# h_sensor_safety.net
KiCad netlist of a schematic drawn in Altium Designer
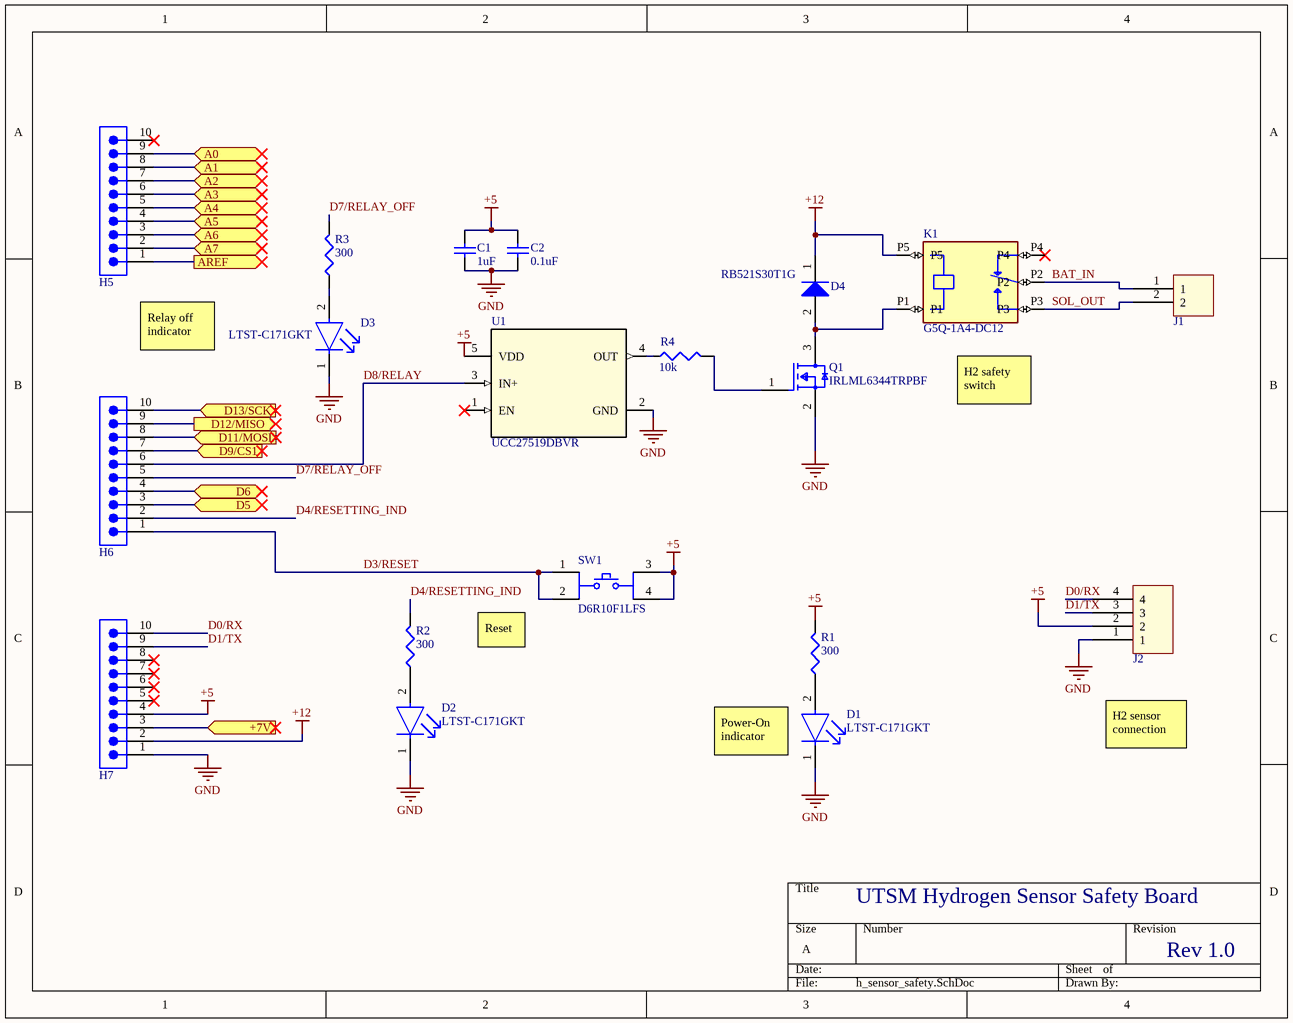
[diagram p0: h_sensor_safety.SchDoc]

(export (version "E")
  (design (tool "Eeschema 10.0.6"))
  (components
    (comp (ref "C1")
      (value "1uF")
      (footprint "0603c")
      (description "0603 Capacitor")
      (fields (field (name "PUBLISHER") "Altium Limited"))
      (libsource (lib "h_sensor_safety") (part "Cap"))
    )
    (comp (ref "C2")
      (value "0.1uF")
      (footprint "0603c")
      (description "0603 Capacitor")
      (fields (field (name "PUBLISHER") "Altium Limited"))
      (libsource (lib "h_sensor_safety") (part "Cap"))
    )
    (comp (ref "D1")
      (value "LTST-C171GKT")
      (footprint "FP-LTST-C171GKT-MFG")
      (description "LED GREEN CLEAR CHIP SMD")
      (libsource (lib "Altium Content Vault") (part "8706943c75ba83719d021d2fdc84c58"))
    )
    (comp (ref "D2")
      (value "LTST-C171GKT")
      (footprint "FP-LTST-C171GKT-MFG")
      (description "LED GREEN CLEAR CHIP SMD")
      (libsource (lib "Altium Content Vault") (part "8706943c75ba83719d021d2fdc84c58"))
    )
    (comp (ref "D3")
      (value "LTST-C171GKT")
      (footprint "FP-LTST-C171GKT-MFG")
      (description "LED GREEN CLEAR CHIP SMD")
      (libsource (lib "Altium Content Vault") (part "8706943c75ba83719d021d2fdc84c58"))
    )
    (comp (ref "D4")
      (value "RB521S30T1G")
      (footprint "ONSC-SOD-523-2-502-01_V")
      (description "Schottky Barrier Diode, 2-Pin SOD-523, Pb-Free, Tape and Reel")
      (fields (field (name "MANUFACTURER") "On Semiconductor"))
      (libsource (lib "Altium Content Vault") (part "ONSC-D-K1A2-2"))
    )
    (comp (ref "H5")
      (value "~")
      (footprint "61301011121")
      (description "WR-PHD Pin Header, THT, Vertical, pitch 2.54mm, 1 Row, 10P")
      (fields
        (field (name "MANUFACTURER PART NUMBER") "61301011121")
        (field (name "MANUFACTURER") "Wurth Elektronik")
      )
      (libsource (lib "h_sensor_safety") (part "61301011121"))
    )
    (comp (ref "H6")
      (value "~")
      (footprint "61301011121")
      (description "WR-PHD Pin Header, THT, Vertical, pitch 2.54mm, 1 Row, 10P")
      (fields
        (field (name "MANUFACTURER PART NUMBER") "61301011121")
        (field (name "MANUFACTURER") "Wurth Elektronik")
      )
      (libsource (lib "h_sensor_safety") (part "61301011121"))
    )
    (comp (ref "H7")
      (value "~")
      (footprint "61301011121")
      (description "WR-PHD Pin Header, THT, Vertical, pitch 2.54mm, 1 Row, 10P")
      (fields
        (field (name "MANUFACTURER PART NUMBER") "61301011121")
        (field (name "MANUFACTURER") "Wurth Elektronik")
      )
      (libsource (lib "h_sensor_safety") (part "61301011121"))
    )
    (comp (ref "J1")
      (value "header 2 pos minifit right angle")
      (footprint "h_sensor_safety:0039300020 minifit 2 pos")
      (libsource (lib "h_sensor_safety") (part "header 2 pos minifit right angle"))
    )
    (comp (ref "J2")
      (value "header 4 pos microfit right angle single row")
      (footprint "0436500401 MICROFIT 4 POS RIGHT ANGLE SINGLE ROW")
      (libsource (lib "h_sensor_safety") (part "header 4 pos microfit right angle single row"))
    )
    (comp (ref "K1")
      (value "G5Q-1A4-DC12")
      (footprint "G5Q-1A4-DC12")
      (fields (field (name "MF") "Omron Electronics"))
      (libsource (lib "h_sensor_safety") (part "G5Q-1A4-DC12"))
    )
    (comp (ref "Q1")
      (value "IRLML6344TRPBF")
      (footprint "FP-Micro3-MFG")
      (description "MOSFET N-CH 30V 2.7A SOT-23-3")
      (fields
        (field (name "MANUFACTURER PART NUMBER") "IRLML2030TRPBF")
        (field (name "OCTOPART") "https://octopart.com/irlml2030trpbf-infineon-65874966")
      )
      (libsource (lib "Altium Content Vault") (part "0a9ea7c96deaaede766a5b531c28de0"))
    )
    (comp (ref "R1")
      (value "300")
      (footprint "0603r")
      (description "SMD Resistor")
      (fields (field (name "Comment") "Res3") (field (name "PUBLISHER") "Altium Limited"))
      (libsource (lib "h_sensor_safety") (part "Res3"))
    )
    (comp (ref "R2")
      (value "300")
      (footprint "0603r")
      (description "SMD Resistor")
      (fields (field (name "Comment") "Res3") (field (name "PUBLISHER") "Altium Limited"))
      (libsource (lib "h_sensor_safety") (part "Res3"))
    )
    (comp (ref "R3")
      (value "300")
      (footprint "0603r")
      (description "SMD Resistor")
      (fields (field (name "Comment") "Res3") (field (name "PUBLISHER") "Altium Limited"))
      (libsource (lib "h_sensor_safety") (part "Res3"))
    )
    (comp (ref "R4")
      (value "10k")
      (footprint "0603r")
      (description "SMD Resistor")
      (fields (field (name "Comment") "Res3") (field (name "PUBLISHER") "Altium Limited"))
      (libsource (lib "h_sensor_safety") (part "Res3"))
    )
    (comp (ref "SW1")
      (value "D6R10F1LFS")
      (footprint "FP-D6R10F1LFS-MFG")
      (description "SWITCH PUSH SPST-NO 0.1A 32V")
      (libsource (lib "Altium Content Vault") (part "14b20f899b8ec0ab38832816b8a4cde"))
    )
    (comp (ref "U1")
      (value "UCC27519DBVR")
      (footprint "SOT95P280X145-5N")
      (description "Low side gate driver")
      (fields
        (field (name "ALTERNATE_PARTNUMBER") "UCC27519DBVT")
        (field (name "MANUFACTURER") "Texas Instruments")
        (field (name "COPYRIGHT") "Copyright (C) 2023 Ultra Librarian. All rights reserved.")
      )
      (libsource (lib "h_sensor_safety") (part "UCC27519DBVR"))
    )
  )
  (nets
    (net (code "1") (name "+5") (class "Default")
      (node (ref "C1") (pin "2") (pinfunction "2_2") (pintype "passive"))
      (node (ref "C2") (pin "2") (pinfunction "2_2") (pintype "passive"))
      (node (ref "H7") (pin "4") (pinfunction "4_4") (pintype "passive"))
      (node (ref "J2") (pin "2") (pinfunction "2_2") (pintype "passive"))
      (node (ref "R1") (pin "2") (pinfunction "2_2") (pintype "passive"))
      (node (ref "SW1") (pin "3") (pinfunction "3_3") (pintype "passive"))
      (node (ref "SW1") (pin "4") (pinfunction "4_4") (pintype "passive"))
      (node (ref "U1") (pin "5") (pinfunction "VDD_5") (pintype "power_in"))
    )
    (net (code "2") (name "+12") (class "Default")
      (node (ref "D4") (pin "1") (pinfunction "K_1") (pintype "passive"))
      (node (ref "H7") (pin "2") (pinfunction "2_2") (pintype "passive"))
      (node (ref "K1") (pin "P5") (pinfunction "P5_P5") (pintype "bidirectional"))
    )
    (net (code "3") (name "/+7V") (class "Default")
      (node (ref "H7") (pin "3") (pinfunction "3_3") (pintype "passive"))
    )
    (net (code "4") (name "/A0") (class "Default")
      (node (ref "H5") (pin "9") (pinfunction "9_9") (pintype "passive"))
    )
    (net (code "5") (name "/A1") (class "Default")
      (node (ref "H5") (pin "8") (pinfunction "8_8") (pintype "passive"))
    )
    (net (code "6") (name "/A2") (class "Default")
      (node (ref "H5") (pin "7") (pinfunction "7_7") (pintype "passive"))
    )
    (net (code "7") (name "/A3") (class "Default")
      (node (ref "H5") (pin "6") (pinfunction "6_6") (pintype "passive"))
    )
    (net (code "8") (name "/A4") (class "Default")
      (node (ref "H5") (pin "5") (pinfunction "5_5") (pintype "passive"))
    )
    (net (code "9") (name "/A5") (class "Default")
      (node (ref "H5") (pin "4") (pinfunction "4_4") (pintype "passive"))
    )
    (net (code "10") (name "/A6") (class "Default")
      (node (ref "H5") (pin "3") (pinfunction "3_3") (pintype "passive"))
    )
    (net (code "11") (name "/A7") (class "Default")
      (node (ref "H5") (pin "2") (pinfunction "2_2") (pintype "passive"))
    )
    (net (code "12") (name "/AREF") (class "Default")
      (node (ref "H5") (pin "1") (pinfunction "1_1") (pintype "passive"))
    )
    (net (code "13") (name "/BAT_IN") (class "Default")
      (node (ref "J1") (pin "1") (pinfunction "1_1") (pintype "passive"))
      (node (ref "K1") (pin "P2") (pinfunction "P2_P2") (pintype "bidirectional"))
    )
    (net (code "14") (name "/D0{slash}RX") (class "Default")
      (node (ref "H7") (pin "10") (pinfunction "10_10") (pintype "passive"))
      (node (ref "J2") (pin "4") (pinfunction "4_4") (pintype "passive"))
    )
    (net (code "15") (name "/D1{slash}TX") (class "Default")
      (node (ref "H7") (pin "9") (pinfunction "9_9") (pintype "passive"))
      (node (ref "J2") (pin "3") (pinfunction "3_3") (pintype "passive"))
    )
    (net (code "16") (name "/D3{slash}RESET") (class "Default")
      (node (ref "H6") (pin "1") (pinfunction "1_1") (pintype "passive"))
      (node (ref "SW1") (pin "1") (pinfunction "1_1") (pintype "passive"))
      (node (ref "SW1") (pin "2") (pinfunction "2_2") (pintype "passive"))
    )
    (net (code "17") (name "/D4{slash}RESETTING_IND") (class "Default")
      (node (ref "H6") (pin "2") (pinfunction "2_2") (pintype "passive"))
      (node (ref "R2") (pin "2") (pinfunction "2_2") (pintype "passive"))
    )
    (net (code "18") (name "/D5") (class "Default")
      (node (ref "H6") (pin "3") (pinfunction "3_3") (pintype "passive"))
    )
    (net (code "19") (name "/D6") (class "Default")
      (node (ref "H6") (pin "4") (pinfunction "4_4") (pintype "passive"))
    )
    (net (code "20") (name "/D7{slash}RELAY_OFF") (class "Default")
      (node (ref "H6") (pin "5") (pinfunction "5_5") (pintype "passive"))
      (node (ref "R3") (pin "2") (pinfunction "2_2") (pintype "passive"))
    )
    (net (code "21") (name "/D8{slash}RELAY") (class "Default")
      (node (ref "H6") (pin "6") (pinfunction "6_6") (pintype "passive"))
      (node (ref "U1") (pin "3") (pinfunction "IN+_3") (pintype "input"))
    )
    (net (code "22") (name "/D9{slash}CS1") (class "Default")
      (node (ref "H6") (pin "7") (pinfunction "7_7") (pintype "passive"))
    )
    (net (code "23") (name "/D11{slash}MOSI") (class "Default")
      (node (ref "H6") (pin "8") (pinfunction "8_8") (pintype "passive"))
    )
    (net (code "24") (name "/D12{slash}MISO") (class "Default")
      (node (ref "H6") (pin "9") (pinfunction "9_9") (pintype "passive"))
    )
    (net (code "25") (name "/D13{slash}SCK") (class "Default")
      (node (ref "H6") (pin "10") (pinfunction "10_10") (pintype "passive"))
    )
    (net (code "26") (name "/SOL_OUT") (class "Default")
      (node (ref "J1") (pin "2") (pinfunction "2_2") (pintype "passive"))
      (node (ref "K1") (pin "P3") (pinfunction "P3_P3") (pintype "bidirectional"))
    )
    (net (code "27") (name "GND") (class "Default")
      (node (ref "C1") (pin "1") (pinfunction "1_1") (pintype "passive"))
      (node (ref "C2") (pin "1") (pinfunction "1_1") (pintype "passive"))
      (node (ref "D1") (pin "1") (pinfunction "C_1") (pintype "passive"))
      (node (ref "D2") (pin "1") (pinfunction "C_1") (pintype "passive"))
      (node (ref "D3") (pin "1") (pinfunction "C_1") (pintype "passive"))
      (node (ref "H7") (pin "1") (pinfunction "1_1") (pintype "passive"))
      (node (ref "J2") (pin "1") (pinfunction "1_1") (pintype "passive"))
      (node (ref "Q1") (pin "2") (pinfunction "S_2") (pintype "passive"))
      (node (ref "U1") (pin "2") (pinfunction "GND_2") (pintype "power_in"))
    )
    (net (code "28") (name "Net-(D1-A)") (class "Default")
      (node (ref "D1") (pin "2") (pinfunction "A_2") (pintype "passive"))
      (node (ref "R1") (pin "1") (pinfunction "1_1") (pintype "passive"))
    )
    (net (code "29") (name "Net-(D2-A)") (class "Default")
      (node (ref "D2") (pin "2") (pinfunction "A_2") (pintype "passive"))
      (node (ref "R2") (pin "1") (pinfunction "1_1") (pintype "passive"))
    )
    (net (code "30") (name "Net-(D3-A)") (class "Default")
      (node (ref "D3") (pin "2") (pinfunction "A_2") (pintype "passive"))
      (node (ref "R3") (pin "1") (pinfunction "1_1") (pintype "passive"))
    )
    (net (code "31") (name "Net-(D4-A)") (class "Default")
      (node (ref "D4") (pin "2") (pinfunction "A_2") (pintype "passive"))
      (node (ref "K1") (pin "P1") (pinfunction "P1_P1") (pintype "bidirectional"))
      (node (ref "Q1") (pin "3") (pinfunction "D_3") (pintype "passive"))
    )
    (net (code "32") (name "Net-(Q1-G)") (class "Default")
      (node (ref "Q1") (pin "1") (pinfunction "G_1") (pintype "passive"))
      (node (ref "R4") (pin "2") (pinfunction "2_2") (pintype "passive"))
    )
    (net (code "33") (name "Net-(U1-OUT)") (class "Default")
      (node (ref "R4") (pin "1") (pinfunction "1_1") (pintype "passive"))
      (node (ref "U1") (pin "4") (pinfunction "OUT_4") (pintype "output"))
    )
    (net (code "34") (name "unconnected-(H5-Pad10)") (class "Default")
      (node (ref "H5") (pin "10") (pinfunction "10_10") (pintype "passive+no_connect"))
    )
    (net (code "35") (name "unconnected-(H7-Pad5)") (class "Default")
      (node (ref "H7") (pin "5") (pinfunction "5_5") (pintype "passive+no_connect"))
    )
    (net (code "36") (name "unconnected-(H7-Pad6)") (class "Default")
      (node (ref "H7") (pin "6") (pinfunction "6_6") (pintype "passive+no_connect"))
    )
    (net (code "37") (name "unconnected-(H7-Pad7)") (class "Default")
      (node (ref "H7") (pin "7") (pinfunction "7_7") (pintype "passive+no_connect"))
    )
    (net (code "38") (name "unconnected-(H7-Pad8)") (class "Default")
      (node (ref "H7") (pin "8") (pinfunction "8_8") (pintype "passive+no_connect"))
    )
    (net (code "39") (name "unconnected-(K1-PadP4)") (class "Default")
      (node (ref "K1") (pin "P4") (pinfunction "P4_P4") (pintype "bidirectional+no_connect"))
    )
    (net (code "40") (name "unconnected-(U1-EN-Pad1)") (class "Default")
      (node (ref "U1") (pin "1") (pinfunction "EN_1") (pintype "input+no_connect"))
    )
  )
)
